# RFID_MQTT_FINAL_ULTIMO_ULTIMO.net
KiCad netlist of a schematic drawn in EAGLE
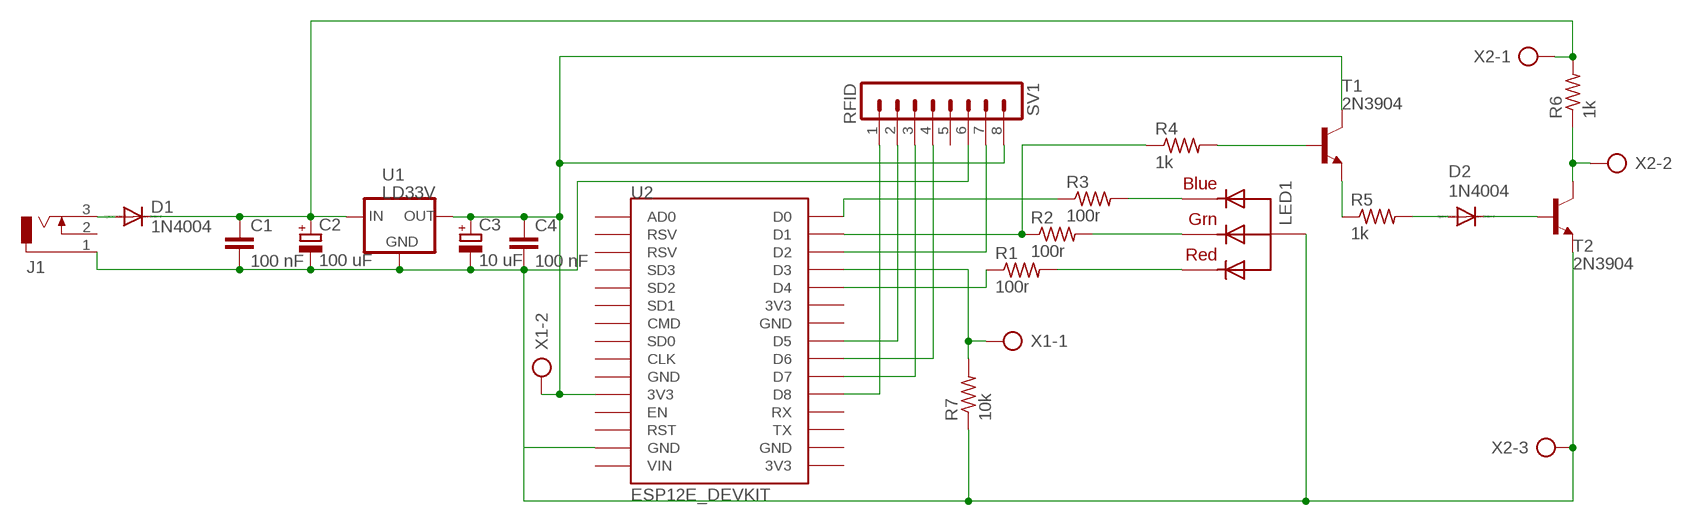
[diagram p0: schematic, sheet 1]

(export (version "E")
  (design (tool "Eeschema 10.0.6"))
  (components
    (comp (ref "C1")
      (value "100 nF")
      (footprint "eagle-import:C050-024X044")
      (libsource (lib "eagle-import") (part "C-EU050-024X044"))
    )
    (comp (ref "C2")
      (value "100 uF")
      (footprint "eagle-import:E3,5-8")
      (libsource (lib "eagle-import") (part "CPOL-EUE3.5-8"))
    )
    (comp (ref "C3")
      (value "10 uF")
      (footprint "eagle-import:E3,5-8")
      (libsource (lib "eagle-import") (part "CPOL-EUE3.5-8"))
    )
    (comp (ref "C4")
      (value "100 nF")
      (footprint "eagle-import:C050-024X044")
      (libsource (lib "eagle-import") (part "C-EU050-024X044"))
    )
    (comp (ref "D1")
      (value "1N4004")
      (footprint "eagle-import:DO41-10")
      (libsource (lib "eagle-import") (part "1N4004"))
    )
    (comp (ref "D2")
      (value "1N4004")
      (footprint "eagle-import:DO41-10")
      (libsource (lib "eagle-import") (part "1N4004"))
    )
    (comp (ref "J1")
      (value "DCJ0202")
      (footprint "eagle-import:DCJ0202")
      (libsource (lib "eagle-import") (part "DCJ0202"))
    )
    (comp (ref "LED1")
      (value "RGBLED_CA-5MM")
      (footprint "eagle-import:LED5MMRGB")
      (libsource (lib "eagle-import") (part "RGBLED_CA-5MM"))
    )
    (comp (ref "R1")
      (value "100r")
      (footprint "eagle-import:0207_7")
      (libsource (lib "eagle-import") (part "R-US_0207/7"))
    )
    (comp (ref "R2")
      (value "100r")
      (footprint "eagle-import:0207_7")
      (libsource (lib "eagle-import") (part "R-US_0207/7"))
    )
    (comp (ref "R3")
      (value "100r")
      (footprint "eagle-import:0207_7")
      (libsource (lib "eagle-import") (part "R-US_0207/7"))
    )
    (comp (ref "R4")
      (value "1k")
      (footprint "eagle-import:0207_7")
      (libsource (lib "eagle-import") (part "R-US_0207/7"))
    )
    (comp (ref "R5")
      (value "1k")
      (footprint "eagle-import:0207_7")
      (libsource (lib "eagle-import") (part "R-US_0207/7"))
    )
    (comp (ref "R6")
      (value "1k")
      (footprint "eagle-import:0207_7")
      (libsource (lib "eagle-import") (part "R-US_0207/7"))
    )
    (comp (ref "R7")
      (value "10k")
      (footprint "eagle-import:0207_7")
      (libsource (lib "eagle-import") (part "R-US_0207/7"))
    )
    (comp (ref "SV1")
      (value "RFID")
      (footprint "eagle-import:MA08-1")
      (libsource (lib "eagle-import") (part "MA08-1"))
    )
    (comp (ref "T1")
      (value "2N3904")
      (footprint "eagle-import:TO92")
      (libsource (lib "eagle-import") (part "2N3904"))
    )
    (comp (ref "T2")
      (value "2N3904")
      (footprint "eagle-import:TO92")
      (libsource (lib "eagle-import") (part "2N3904"))
    )
    (comp (ref "U1")
      (value "LD33V")
      (footprint "eagle-import:LD1117V33")
      (libsource (lib "eagle-import") (part "LD1117V33"))
    )
    (comp (ref "U2")
      (value "ESP12E_DEVKIT")
      (footprint "eagle-import:ESP12E_DEVKIT")
      (libsource (lib "eagle-import") (part "ESP12E_DEVKIT"))
    )
    (comp (ref "X1")
      (value "AK500/2-H")
      (footprint "eagle-import:AK500_2-H")
      (libsource (lib "eagle-import") (part "AK500/2-H"))
    )
    (comp (ref "X2")
      (value "AK500/3-H")
      (footprint "eagle-import:AK500_3-H")
      (libsource (lib "eagle-import") (part "AK500/3-H"))
    )
  )
  (nets
    (net (code "1") (name "Net-(D1-PadA)") (class "Default")
      (node (ref "D1") (pin "A") (pinfunction "A_A") (pintype "passive"))
      (node (ref "J1") (pin "3") (pinfunction "3_3") (pintype "passive"))
    )
    (net (code "2") (name "Net-(D2-PadA)") (class "Default")
      (node (ref "D2") (pin "A") (pinfunction "A_A") (pintype "passive"))
      (node (ref "R5") (pin "2") (pinfunction "2_2") (pintype "passive"))
    )
    (net (code "3") (name "Net-(LED1-BLUE)") (class "Default")
      (node (ref "LED1") (pin "4") (pinfunction "BLUE_4") (pintype "bidirectional"))
      (node (ref "R3") (pin "2") (pinfunction "2_2") (pintype "passive"))
    )
    (net (code "4") (name "Net-(LED1-GREEN)") (class "Default")
      (node (ref "LED1") (pin "3") (pinfunction "GREEN_3") (pintype "bidirectional"))
      (node (ref "R2") (pin "2") (pinfunction "2_2") (pintype "passive"))
    )
    (net (code "5") (name "Net-(LED1-RED)") (class "Default")
      (node (ref "LED1") (pin "1") (pinfunction "RED_1") (pintype "bidirectional"))
      (node (ref "R1") (pin "2") (pinfunction "2_2") (pintype "passive"))
    )
    (net (code "6") (name "Net-(LED1-VCC)") (class "Default")
      (node (ref "C1") (pin "2") (pinfunction "2_2") (pintype "passive"))
      (node (ref "C2") (pin "-") (pinfunction "-_-") (pintype "passive"))
      (node (ref "C3") (pin "-") (pinfunction "-_-") (pintype "passive"))
      (node (ref "C4") (pin "2") (pinfunction "2_2") (pintype "passive"))
      (node (ref "J1") (pin "1") (pinfunction "1_1") (pintype "passive"))
      (node (ref "LED1") (pin "2") (pinfunction "VCC_2") (pintype "bidirectional"))
      (node (ref "R7") (pin "1") (pinfunction "1_1") (pintype "passive"))
      (node (ref "SV1") (pin "6") (pinfunction "6_6") (pintype "passive"))
      (node (ref "T2") (pin "3") (pinfunction "E_3") (pintype "passive"))
      (node (ref "U1") (pin "GND") (pinfunction "GND_GND") (pintype "input"))
      (node (ref "U2") (pin "GND@1") (pinfunction "GND_GND@1") (pintype "bidirectional"))
      (node (ref "X2") (pin "3") (pinfunction "KL_3") (pintype "passive"))
    )
    (net (code "7") (name "Net-(R1-Pad1)") (class "Default")
      (node (ref "R1") (pin "1") (pinfunction "1_1") (pintype "passive"))
      (node (ref "U2") (pin "D4") (pinfunction "D4_D4") (pintype "bidirectional"))
    )
    (net (code "8") (name "Net-(R2-Pad1)") (class "Default")
      (node (ref "R2") (pin "1") (pinfunction "1_1") (pintype "passive"))
      (node (ref "R4") (pin "1") (pinfunction "1_1") (pintype "passive"))
      (node (ref "U2") (pin "D1") (pinfunction "D1_D1") (pintype "bidirectional"))
    )
    (net (code "9") (name "Net-(R3-Pad1)") (class "Default")
      (node (ref "R3") (pin "1") (pinfunction "1_1") (pintype "passive"))
      (node (ref "U2") (pin "D0") (pinfunction "D0_D0") (pintype "bidirectional"))
    )
    (net (code "10") (name "Net-(SV1-Pad1)") (class "Default")
      (node (ref "SV1") (pin "1") (pinfunction "1_1") (pintype "passive"))
      (node (ref "U2") (pin "D8") (pinfunction "D8_D8") (pintype "bidirectional"))
    )
    (net (code "11") (name "Net-(SV1-Pad2)") (class "Default")
      (node (ref "SV1") (pin "2") (pinfunction "2_2") (pintype "passive"))
      (node (ref "U2") (pin "D5") (pinfunction "D5_D5") (pintype "bidirectional"))
    )
    (net (code "12") (name "Net-(SV1-Pad3)") (class "Default")
      (node (ref "SV1") (pin "3") (pinfunction "3_3") (pintype "passive"))
      (node (ref "U2") (pin "D7") (pinfunction "D7_D7") (pintype "bidirectional"))
    )
    (net (code "13") (name "Net-(SV1-Pad4)") (class "Default")
      (node (ref "SV1") (pin "4") (pinfunction "4_4") (pintype "passive"))
      (node (ref "U2") (pin "D6") (pinfunction "D6_D6") (pintype "bidirectional"))
    )
    (net (code "14") (name "Net-(SV1-Pad7)") (class "Default")
      (node (ref "SV1") (pin "7") (pinfunction "7_7") (pintype "passive"))
      (node (ref "U2") (pin "D2") (pinfunction "D2_D2") (pintype "bidirectional"))
    )
    (net (code "15") (name "Net-(T1-B)") (class "Default")
      (node (ref "R4") (pin "2") (pinfunction "2_2") (pintype "passive"))
      (node (ref "T1") (pin "2") (pinfunction "B_2") (pintype "passive"))
    )
    (net (code "16") (name "Net-(T1-C)") (class "Default")
      (node (ref "C3") (pin "+") (pinfunction "+_+") (pintype "passive"))
      (node (ref "C4") (pin "1") (pinfunction "1_1") (pintype "passive"))
      (node (ref "SV1") (pin "8") (pinfunction "8_8") (pintype "passive"))
      (node (ref "T1") (pin "1") (pinfunction "C_1") (pintype "passive"))
      (node (ref "U1") (pin "OUT") (pinfunction "OUT_OUT") (pintype "output"))
      (node (ref "U2") (pin "3V3@0") (pinfunction "3V3_3V3@0") (pintype "bidirectional"))
      (node (ref "X1") (pin "2") (pinfunction "KL_2") (pintype "passive"))
    )
    (net (code "17") (name "Net-(T1-E)") (class "Default")
      (node (ref "R5") (pin "1") (pinfunction "1_1") (pintype "passive"))
      (node (ref "T1") (pin "3") (pinfunction "E_3") (pintype "passive"))
    )
    (net (code "18") (name "Net-(T2-B)") (class "Default")
      (node (ref "D2") (pin "C") (pinfunction "C_C") (pintype "passive"))
      (node (ref "T2") (pin "2") (pinfunction "B_2") (pintype "passive"))
    )
    (net (code "19") (name "Net-(T2-C)") (class "Default")
      (node (ref "R6") (pin "1") (pinfunction "1_1") (pintype "passive"))
      (node (ref "T2") (pin "1") (pinfunction "C_1") (pintype "passive"))
      (node (ref "X2") (pin "2") (pinfunction "KL_2") (pintype "passive"))
    )
    (net (code "20") (name "Net-(X1A-KL)") (class "Default")
      (node (ref "R7") (pin "2") (pinfunction "2_2") (pintype "passive"))
      (node (ref "U2") (pin "D3") (pinfunction "D3_D3") (pintype "bidirectional"))
      (node (ref "X1") (pin "1") (pinfunction "KL_1") (pintype "passive"))
    )
    (net (code "21") (name "Net-(X2A-KL)") (class "Default")
      (node (ref "C1") (pin "1") (pinfunction "1_1") (pintype "passive"))
      (node (ref "C2") (pin "+") (pinfunction "+_+") (pintype "passive"))
      (node (ref "D1") (pin "C") (pinfunction "C_C") (pintype "passive"))
      (node (ref "R6") (pin "2") (pinfunction "2_2") (pintype "passive"))
      (node (ref "U1") (pin "IN") (pinfunction "IN_IN") (pintype "input"))
      (node (ref "X2") (pin "1") (pinfunction "KL_1") (pintype "passive"))
    )
    (net (code "22") (name "unconnected-(J1-Pad2)") (class "Default")
      (node (ref "J1") (pin "2") (pinfunction "2_2") (pintype "passive"))
    )
    (net (code "23") (name "unconnected-(SV1-Pad5)") (class "Default")
      (node (ref "SV1") (pin "5") (pinfunction "5_5") (pintype "passive"))
    )
    (net (code "24") (name "unconnected-(U2-3V3-Pad3V3@1)") (class "Default")
      (node (ref "U2") (pin "3V3@1") (pinfunction "3V3_3V3@1") (pintype "bidirectional"))
    )
    (net (code "25") (name "unconnected-(U2-3V3-Pad3V3@2)") (class "Default")
      (node (ref "U2") (pin "3V3@2") (pinfunction "3V3_3V3@2") (pintype "bidirectional"))
    )
    (net (code "26") (name "unconnected-(U2-GND-PadGND@0)") (class "Default")
      (node (ref "U2") (pin "GND@0") (pinfunction "GND_GND@0") (pintype "bidirectional"))
    )
    (net (code "27") (name "unconnected-(U2-GND-PadGND@2)") (class "Default")
      (node (ref "U2") (pin "GND@2") (pinfunction "GND_GND@2") (pintype "bidirectional"))
    )
    (net (code "28") (name "unconnected-(U2-GND-PadGND@3)") (class "Default")
      (node (ref "U2") (pin "GND@3") (pinfunction "GND_GND@3") (pintype "bidirectional"))
    )
    (net (code "29") (name "unconnected-(U2-PadAD0)") (class "Default")
      (node (ref "U2") (pin "AD0") (pinfunction "AD0_AD0") (pintype "bidirectional"))
    )
    (net (code "30") (name "unconnected-(U2-PadCLK)") (class "Default")
      (node (ref "U2") (pin "CLK") (pinfunction "CLK_CLK") (pintype "bidirectional"))
    )
    (net (code "31") (name "unconnected-(U2-PadCMD)") (class "Default")
      (node (ref "U2") (pin "CMD") (pinfunction "CMD_CMD") (pintype "bidirectional"))
    )
    (net (code "32") (name "unconnected-(U2-PadEN)") (class "Default")
      (node (ref "U2") (pin "EN") (pinfunction "EN_EN") (pintype "bidirectional"))
    )
    (net (code "33") (name "unconnected-(U2-PadRST)") (class "Default")
      (node (ref "U2") (pin "RST") (pinfunction "RST_RST") (pintype "bidirectional"))
    )
    (net (code "34") (name "unconnected-(U2-PadRX)") (class "Default")
      (node (ref "U2") (pin "RX") (pinfunction "RX_RX") (pintype "bidirectional"))
    )
    (net (code "35") (name "unconnected-(U2-PadSD0)") (class "Default")
      (node (ref "U2") (pin "SD0") (pinfunction "SD0_SD0") (pintype "bidirectional"))
    )
    (net (code "36") (name "unconnected-(U2-PadSD1)") (class "Default")
      (node (ref "U2") (pin "SD1") (pinfunction "SD1_SD1") (pintype "bidirectional"))
    )
    (net (code "37") (name "unconnected-(U2-PadSD2)") (class "Default")
      (node (ref "U2") (pin "SD2") (pinfunction "SD2_SD2") (pintype "bidirectional"))
    )
    (net (code "38") (name "unconnected-(U2-PadSD3)") (class "Default")
      (node (ref "U2") (pin "SD3") (pinfunction "SD3_SD3") (pintype "bidirectional"))
    )
    (net (code "39") (name "unconnected-(U2-PadTX)") (class "Default")
      (node (ref "U2") (pin "TX") (pinfunction "TX_TX") (pintype "bidirectional"))
    )
    (net (code "40") (name "unconnected-(U2-PadVIN)") (class "Default")
      (node (ref "U2") (pin "VIN") (pinfunction "VIN_VIN") (pintype "bidirectional"))
    )
    (net (code "41") (name "unconnected-(U2-RSV-PadRSV@0)") (class "Default")
      (node (ref "U2") (pin "RSV@0") (pinfunction "RSV_RSV@0") (pintype "bidirectional"))
    )
    (net (code "42") (name "unconnected-(U2-RSV-PadRSV@1)") (class "Default")
      (node (ref "U2") (pin "RSV@1") (pinfunction "RSV_RSV@1") (pintype "bidirectional"))
    )
  )
)
